# zzh.net
KiCad netlist of a schematic drawn in EAGLE
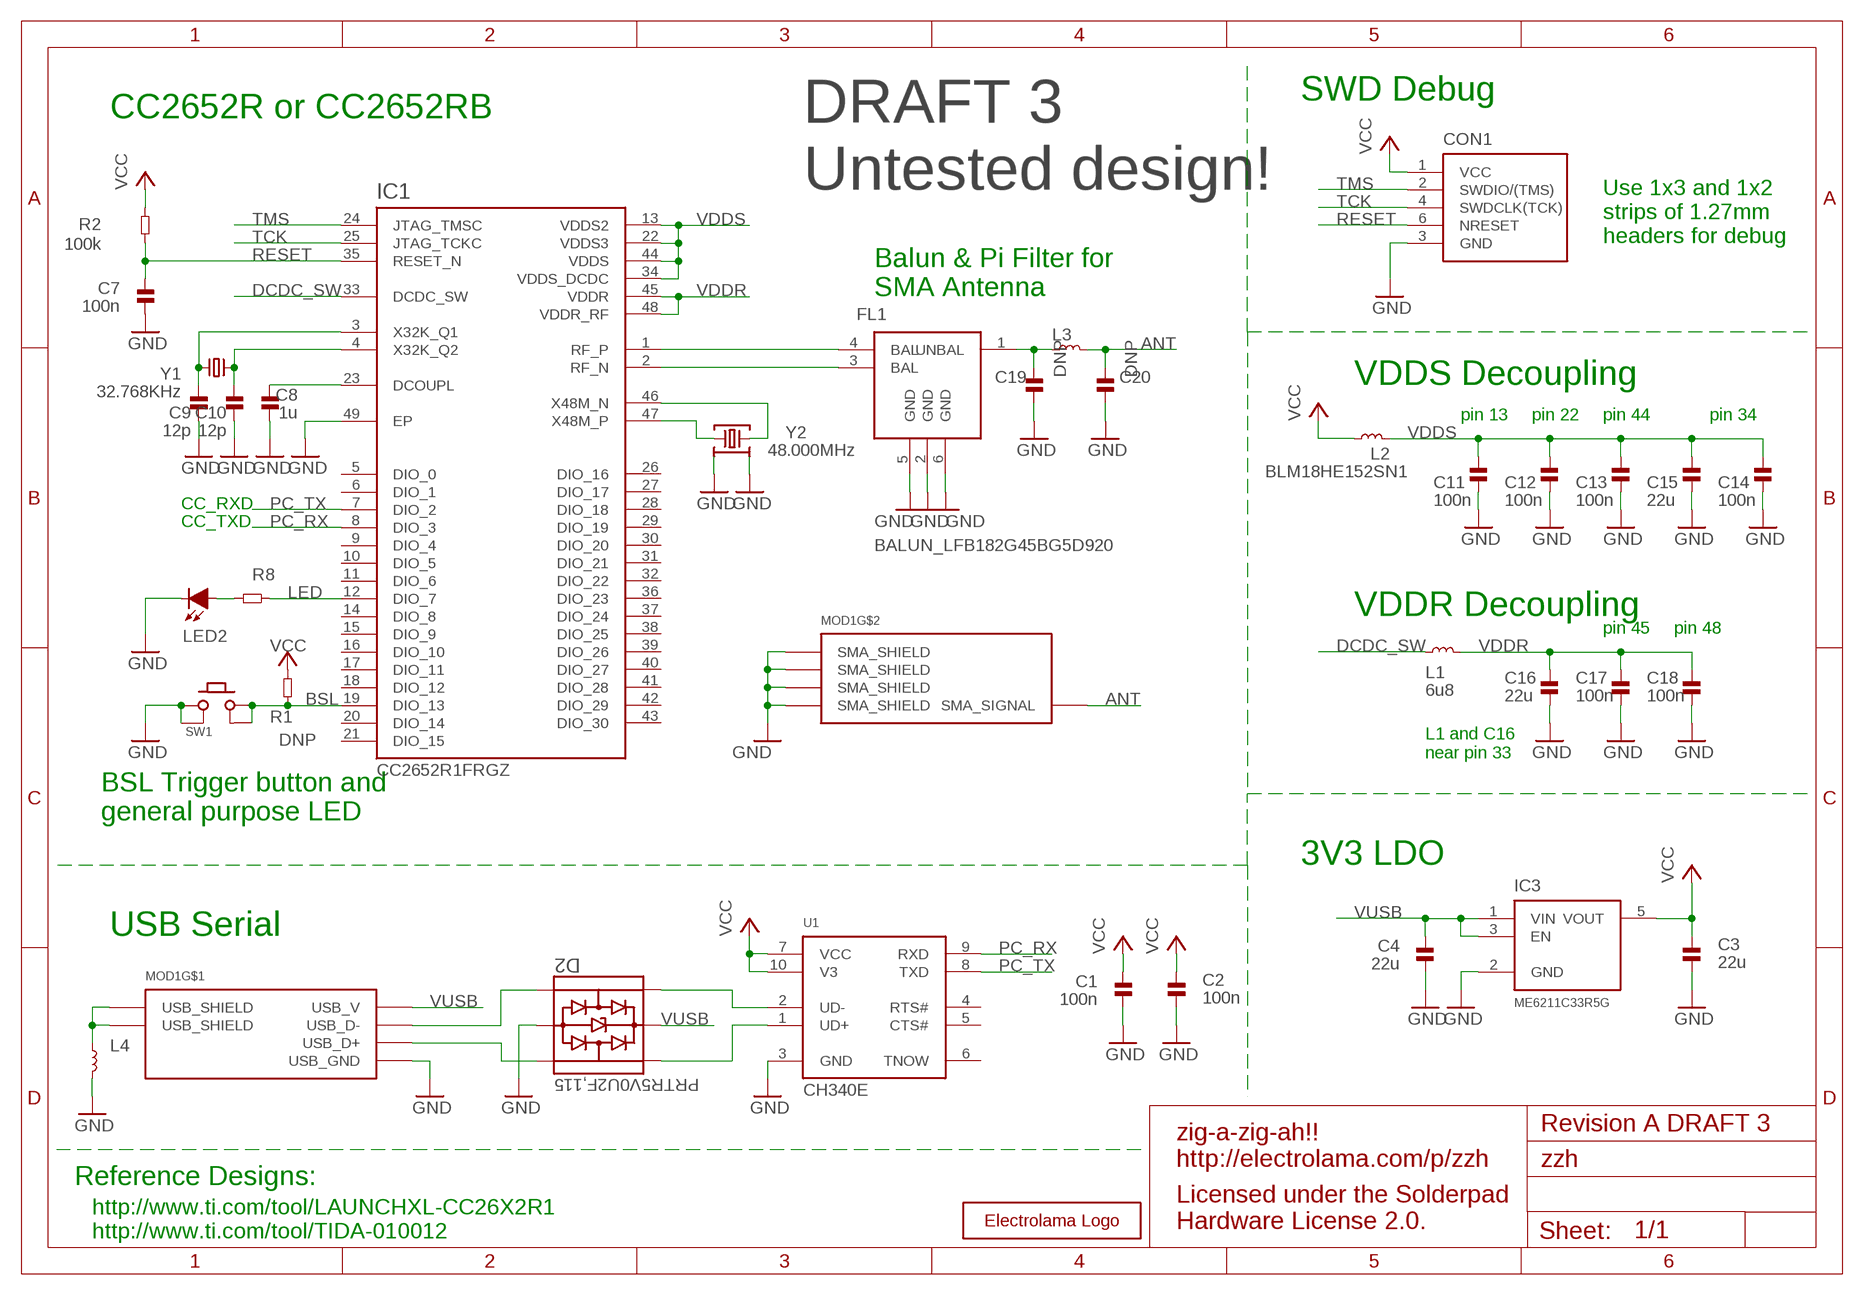
[diagram p0: schematic, sheet 1]

(export (version "E")
  (design (tool "Eeschema 10.0.6"))
  (components
    (comp (ref "C1")
      (value "100n")
      (footprint "eagle-import:_PKG_C_0402")
      (libsource (lib "eagle-import") (part "CAP-0402"))
    )
    (comp (ref "C2")
      (value "100n")
      (footprint "eagle-import:_PKG_C_0402")
      (libsource (lib "eagle-import") (part "CAP-0402"))
    )
    (comp (ref "C3")
      (value "22u")
      (footprint "eagle-import:_PKG_C_0805")
      (libsource (lib "eagle-import") (part "CAP-0805"))
    )
    (comp (ref "C4")
      (value "22u")
      (footprint "eagle-import:_PKG_C_0805")
      (libsource (lib "eagle-import") (part "CAP-0805"))
    )
    (comp (ref "C7")
      (value "100n")
      (footprint "eagle-import:_PKG_C_0402")
      (libsource (lib "eagle-import") (part "CAP-0402"))
    )
    (comp (ref "C8")
      (value "1u")
      (footprint "eagle-import:_PKG_C_0402")
      (libsource (lib "eagle-import") (part "CAP-0402"))
    )
    (comp (ref "C9")
      (value "12p")
      (footprint "eagle-import:_PKG_C_0402")
      (libsource (lib "eagle-import") (part "CAP-0402"))
    )
    (comp (ref "C10")
      (value "12p")
      (footprint "eagle-import:_PKG_C_0402")
      (libsource (lib "eagle-import") (part "CAP-0402"))
    )
    (comp (ref "C11")
      (value "100n")
      (footprint "eagle-import:_PKG_C_0402")
      (libsource (lib "eagle-import") (part "CAP-0402"))
    )
    (comp (ref "C12")
      (value "100n")
      (footprint "eagle-import:_PKG_C_0402")
      (libsource (lib "eagle-import") (part "CAP-0402"))
    )
    (comp (ref "C13")
      (value "100n")
      (footprint "eagle-import:_PKG_C_0402")
      (libsource (lib "eagle-import") (part "CAP-0402"))
    )
    (comp (ref "C14")
      (value "100n")
      (footprint "eagle-import:_PKG_C_0402")
      (libsource (lib "eagle-import") (part "CAP-0402"))
    )
    (comp (ref "C15")
      (value "22u")
      (footprint "eagle-import:_PKG_C_0805")
      (libsource (lib "eagle-import") (part "CAP-0805"))
    )
    (comp (ref "C16")
      (value "22u")
      (footprint "eagle-import:_PKG_C_0805")
      (libsource (lib "eagle-import") (part "CAP-0805"))
    )
    (comp (ref "C17")
      (value "100n")
      (footprint "eagle-import:_PKG_C_0402")
      (libsource (lib "eagle-import") (part "CAP-0402"))
    )
    (comp (ref "C18")
      (value "100n")
      (footprint "eagle-import:_PKG_C_0402")
      (libsource (lib "eagle-import") (part "CAP-0402"))
    )
    (comp (ref "C19")
      (value "DNP")
      (footprint "eagle-import:_PKG_C_0402")
      (libsource (lib "eagle-import") (part "CAP-0402"))
    )
    (comp (ref "C20")
      (value "DNP")
      (footprint "eagle-import:_PKG_C_0402")
      (libsource (lib "eagle-import") (part "CAP-0402"))
    )
    (comp (ref "CON1")
      (value "DEBUG_CORTEX-SWD-5PIN-CUT5")
      (footprint "eagle-import:DEBUG_CORTEX_5PIN")
      (libsource (lib "eagle-import") (part "DEBUG_CORTEX-SWD-5PIN-CUT5"))
    )
    (comp (ref "D2")
      (value "PRTR5V0U2F,115")
      (footprint "eagle-import:_PKG_SOT886_JEDEC-MO-252")
      (fields
        (field (name "MOUSER_PART_NUMBER") "771-PRTR5V0U2F-T/R")
        (field (name "RS_PART_NUMBER") "8166931P")
      )
      (libsource (lib "eagle-import") (part "DIODE-TVS-PRTR5V0U2F{dblquote}"))
    )
    (comp (ref "FL1")
      (value "BALUN_LFB182G45BG5D920")
      (footprint "eagle-import:LFB182G45BG5D920")
      (fields
        (field (name "MANUFACTURER_PART_NUMBER") "LFB182G45BG5D920")
        (field (name "MOUSER_PART_NUMBER") "81-LFB182G45BG5D920")
      )
      (libsource (lib "eagle-import") (part "BALUN_LFB182G45BG5D920"))
    )
    (comp (ref "IC1")
      (value "CC2652R1FRGZ")
      (footprint "eagle-import:QFN50P700X700X100-49N")
      (fields
        (field (name "MANUFACTURER_PART_NUMBER") "CC2652R1FRGZT")
        (field (name "MOUSER_PART_NUMBER") "595-CC2652R1FRGZT")
      )
      (libsource (lib "eagle-import") (part "WMCU-CC2652R1FRGZ"))
    )
    (comp (ref "IC3")
      (value "ME6211C33R5G")
      (footprint "eagle-import:SOT65P212X110-5N")
      (libsource (lib "eagle-import") (part "POWER-LDO-ME6211C33R5G"))
    )
    (comp (ref "L1")
      (value "6u8")
      (footprint "eagle-import:_PKG_C_0805")
      (libsource (lib "eagle-import") (part "INDUCTOR-0805"))
    )
    (comp (ref "L2")
      (value "BLM18HE152SN1")
      (footprint "eagle-import:_PKG_L_0603")
      (libsource (lib "eagle-import") (part "INDUCTOR-0603"))
    )
    (comp (ref "L3")
      (value "INDUCTOR-0402")
      (footprint "eagle-import:_PKG_L_0402")
      (libsource (lib "eagle-import") (part "INDUCTOR-0402"))
    )
    (comp (ref "L4")
      (value "INDUCTOR-0402")
      (footprint "eagle-import:_PKG_L_0402")
      (libsource (lib "eagle-import") (part "INDUCTOR-0402"))
    )
    (comp (ref "LED2")
      (value "LED-0603")
      (footprint "eagle-import:_PKG_LED_0603")
      (libsource (lib "eagle-import") (part "LED-0603"))
    )
    (comp (ref "MOD1")
      (value "ZZH_MODULE")
      (footprint "eagle-import:ZZH_MODULE")
      (libsource (lib "eagle-import") (part "ZZH_MODULE"))
    )
    (comp (ref "R1")
      (value "DNP")
      (footprint "eagle-import:_PKG_C_0402")
      (libsource (lib "eagle-import") (part "RES-0402"))
    )
    (comp (ref "R2")
      (value "100k")
      (footprint "eagle-import:_PKG_C_0402")
      (libsource (lib "eagle-import") (part "RES-0402"))
    )
    (comp (ref "R8")
      (value "RES-0402")
      (footprint "eagle-import:_PKG_C_0402")
      (libsource (lib "eagle-import") (part "RES-0402"))
    )
    (comp (ref "SW1")
      (value "K2-1177SW-D4DW-06")
      (footprint "eagle-import:K2-1177SW-D4DW-06")
      (libsource (lib "eagle-import") (part "PUSHBUTTON-K2-1177SW-D4DW-06"))
    )
    (comp (ref "U$5")
      (value "LOGO-ELECTROLAMA")
      (footprint "eagle-import:ELECTROLAMA")
      (libsource (lib "eagle-import") (part "LOGO-ELECTROLAMA"))
    )
    (comp (ref "U1")
      (value "CH340E")
      (footprint "eagle-import:_PKG_MSOP10_TI-DGS10")
      (libsource (lib "eagle-import") (part "INTERFACE-CH340E"))
    )
    (comp (ref "Y1")
      (value "32.768KHz")
      (footprint "eagle-import:XTAL-2P-3215")
      (fields (field (name "LCSC_PART") "C32346") (field (name "MFG_PART") "Q13FC1350000400"))
      (libsource (lib "eagle-import") (part "32.768KHZ_Q13FC1350000400"))
    )
    (comp (ref "Y2")
      (value "48.000MHz")
      (footprint "eagle-import:XTAL-4P-2016")
      (fields (field (name "DIGIKEY_PART") "1253-2042-1-ND") (field (name "MFG_PART") "CX2016DB48000C0FPLC1"))
      (libsource (lib "eagle-import") (part "48.000MHZ_CX2016DB48000C0FPLC1"))
    )
  )
  (nets
    (net (code "1") (name "/ANT") (class "Default")
      (node (ref "C20") (pin "2") (pinfunction "2_2") (pintype "passive"))
      (node (ref "L3") (pin "2") (pinfunction "2_2") (pintype "passive"))
      (node (ref "MOD1") (pin "SMA_SIGNAL") (pinfunction "SMA_SIGNAL_SMA_SIGNAL") (pintype "bidirectional"))
    )
    (net (code "2") (name "/BSL") (class "Default")
      (node (ref "IC1") (pin "19") (pinfunction "DIO_13_19") (pintype "bidirectional"))
      (node (ref "R1") (pin "2") (pinfunction "2_2") (pintype "passive"))
      (node (ref "SW1") (pin "3") (pinfunction "2_1_3") (pintype "bidirectional"))
      (node (ref "SW1") (pin "4") (pinfunction "2_2_4") (pintype "bidirectional"))
    )
    (net (code "3") (name "/DCDC_SW") (class "Default")
      (node (ref "IC1") (pin "33") (pinfunction "DCDC_SW_33") (pintype "bidirectional"))
      (node (ref "L1") (pin "1") (pinfunction "1_1") (pintype "passive"))
    )
    (net (code "4") (name "/LED") (class "Default")
      (node (ref "IC1") (pin "12") (pinfunction "DIO_7_12") (pintype "bidirectional"))
      (node (ref "R8") (pin "1") (pinfunction "1_1") (pintype "passive"))
    )
    (net (code "6") (name "/PC_RX") (class "Default")
      (node (ref "IC1") (pin "8") (pinfunction "DIO_3_8") (pintype "bidirectional"))
      (node (ref "U1") (pin "9") (pinfunction "RXD_9") (pintype "bidirectional"))
    )
    (net (code "7") (name "/PC_TX") (class "Default")
      (node (ref "IC1") (pin "7") (pinfunction "DIO_2_7") (pintype "bidirectional"))
      (node (ref "U1") (pin "8") (pinfunction "TXD_8") (pintype "bidirectional"))
    )
    (net (code "8") (name "/RESET") (class "Default")
      (node (ref "C7") (pin "2") (pinfunction "2_2") (pintype "passive"))
      (node (ref "CON1") (pin "6") (pinfunction "NRESET_6") (pintype "bidirectional"))
      (node (ref "IC1") (pin "35") (pinfunction "RESET_N_35") (pintype "bidirectional"))
      (node (ref "R2") (pin "1") (pinfunction "1_1") (pintype "passive"))
    )
    (net (code "9") (name "/TCK") (class "Default")
      (node (ref "CON1") (pin "4") (pinfunction "SWDCLK(TCK)_4") (pintype "bidirectional"))
      (node (ref "IC1") (pin "25") (pinfunction "JTAG_TCKC_25") (pintype "bidirectional"))
    )
    (net (code "10") (name "/TMS") (class "Default")
      (node (ref "CON1") (pin "2") (pinfunction "SWDIO/(TMS)_2") (pintype "bidirectional"))
      (node (ref "IC1") (pin "24") (pinfunction "JTAG_TMSC_24") (pintype "bidirectional"))
    )
    (net (code "11") (name "/VDDR") (class "Default")
      (node (ref "C16") (pin "1") (pinfunction "1_1") (pintype "passive"))
      (node (ref "C17") (pin "1") (pinfunction "1_1") (pintype "passive"))
      (node (ref "C18") (pin "1") (pinfunction "1_1") (pintype "passive"))
      (node (ref "IC1") (pin "45") (pinfunction "VDDR_45") (pintype "bidirectional"))
      (node (ref "IC1") (pin "48") (pinfunction "VDDR_RF_48") (pintype "bidirectional"))
      (node (ref "L1") (pin "2") (pinfunction "2_2") (pintype "passive"))
    )
    (net (code "12") (name "/VDDS") (class "Default")
      (node (ref "C11") (pin "1") (pinfunction "1_1") (pintype "passive"))
      (node (ref "C12") (pin "1") (pinfunction "1_1") (pintype "passive"))
      (node (ref "C13") (pin "1") (pinfunction "1_1") (pintype "passive"))
      (node (ref "C14") (pin "1") (pinfunction "1_1") (pintype "passive"))
      (node (ref "C15") (pin "1") (pinfunction "1_1") (pintype "passive"))
      (node (ref "IC1") (pin "13") (pinfunction "VDDS2_13") (pintype "bidirectional"))
      (node (ref "IC1") (pin "22") (pinfunction "VDDS3_22") (pintype "bidirectional"))
      (node (ref "IC1") (pin "34") (pinfunction "VDDS_DCDC_34") (pintype "bidirectional"))
      (node (ref "IC1") (pin "44") (pinfunction "VDDS_44") (pintype "bidirectional"))
      (node (ref "L2") (pin "2") (pinfunction "2_2") (pintype "passive"))
    )
    (net (code "13") (name "/VUSB") (class "Default")
      (node (ref "C4") (pin "1") (pinfunction "1_1") (pintype "passive"))
      (node (ref "D2") (pin "5") (pinfunction "5_5") (pintype "passive"))
      (node (ref "IC3") (pin "1") (pinfunction "VIN_1") (pintype "bidirectional"))
      (node (ref "IC3") (pin "3") (pinfunction "EN_3") (pintype "bidirectional"))
      (node (ref "MOD1") (pin "USB_V") (pinfunction "USB_V_USB_V") (pintype "bidirectional"))
    )
    (net (code "14") (name "GND") (class "Default")
      (node (ref "C1") (pin "1") (pinfunction "1_1") (pintype "passive"))
      (node (ref "C10") (pin "1") (pinfunction "1_1") (pintype "passive"))
      (node (ref "C11") (pin "2") (pinfunction "2_2") (pintype "passive"))
      (node (ref "C12") (pin "2") (pinfunction "2_2") (pintype "passive"))
      (node (ref "C13") (pin "2") (pinfunction "2_2") (pintype "passive"))
      (node (ref "C14") (pin "2") (pinfunction "2_2") (pintype "passive"))
      (node (ref "C15") (pin "2") (pinfunction "2_2") (pintype "passive"))
      (node (ref "C16") (pin "2") (pinfunction "2_2") (pintype "passive"))
      (node (ref "C17") (pin "2") (pinfunction "2_2") (pintype "passive"))
      (node (ref "C18") (pin "2") (pinfunction "2_2") (pintype "passive"))
      (node (ref "C19") (pin "1") (pinfunction "1_1") (pintype "passive"))
      (node (ref "C2") (pin "1") (pinfunction "1_1") (pintype "passive"))
      (node (ref "C20") (pin "1") (pinfunction "1_1") (pintype "passive"))
      (node (ref "C3") (pin "2") (pinfunction "2_2") (pintype "passive"))
      (node (ref "C4") (pin "2") (pinfunction "2_2") (pintype "passive"))
      (node (ref "C7") (pin "1") (pinfunction "1_1") (pintype "passive"))
      (node (ref "C8") (pin "1") (pinfunction "1_1") (pintype "passive"))
      (node (ref "C9") (pin "1") (pinfunction "1_1") (pintype "passive"))
      (node (ref "CON1") (pin "3") (pinfunction "GND_3") (pintype "bidirectional"))
      (node (ref "D2") (pin "2") (pinfunction "2_2") (pintype "passive"))
      (node (ref "FL1") (pin "2") (pinfunction "GND_2") (pintype "bidirectional"))
      (node (ref "FL1") (pin "5") (pinfunction "GND_5") (pintype "bidirectional"))
      (node (ref "FL1") (pin "6") (pinfunction "GND_6") (pintype "bidirectional"))
      (node (ref "IC1") (pin "49") (pinfunction "EP_49") (pintype "bidirectional"))
      (node (ref "IC3") (pin "2") (pinfunction "GND_2") (pintype "bidirectional"))
      (node (ref "L4") (pin "2") (pinfunction "2_2") (pintype "passive"))
      (node (ref "LED2") (pin "C") (pinfunction "C_C") (pintype "passive"))
      (node (ref "MOD1") (pin "SMA_SHIELD_1") (pinfunction "SMA_SHIELD_SMA_SHIELD_1") (pintype "bidirectional"))
      (node (ref "MOD1") (pin "SMA_SHIELD_2") (pinfunction "SMA_SHIELD_SMA_SHIELD_2") (pintype "bidirectional"))
      (node (ref "MOD1") (pin "SMA_SHIELD_3") (pinfunction "SMA_SHIELD_SMA_SHIELD_3") (pintype "bidirectional"))
      (node (ref "MOD1") (pin "SMA_SHIELD_4") (pinfunction "SMA_SHIELD_SMA_SHIELD_4") (pintype "bidirectional"))
      (node (ref "MOD1") (pin "USB_GND") (pinfunction "USB_GND_USB_GND") (pintype "bidirectional"))
      (node (ref "SW1") (pin "1") (pinfunction "1_1_1") (pintype "bidirectional"))
      (node (ref "SW1") (pin "2") (pinfunction "1_2_2") (pintype "bidirectional"))
      (node (ref "U1") (pin "3") (pinfunction "GND_3") (pintype "bidirectional"))
      (node (ref "Y2") (pin "2") (pinfunction "2_2") (pintype "bidirectional"))
      (node (ref "Y2") (pin "4") (pinfunction "4_4") (pintype "bidirectional"))
    )
    (net (code "15") (name "Net-(D2-Pad1)") (class "Default")
      (node (ref "D2") (pin "1") (pinfunction "1_1") (pintype "passive"))
      (node (ref "MOD1") (pin "USB_D+") (pinfunction "USB_D+_USB_D+") (pintype "bidirectional"))
    )
    (net (code "16") (name "Net-(D2-Pad3)") (class "Default")
      (node (ref "D2") (pin "3") (pinfunction "3_3") (pintype "passive"))
      (node (ref "MOD1") (pin "USB_D-") (pinfunction "USB_D-_USB_D-") (pintype "bidirectional"))
    )
    (net (code "17") (name "Net-(FL1-UNBAL)") (class "Default")
      (node (ref "C19") (pin "2") (pinfunction "2_2") (pintype "passive"))
      (node (ref "FL1") (pin "1") (pinfunction "UNBAL_1") (pintype "bidirectional"))
      (node (ref "L3") (pin "1") (pinfunction "1_1") (pintype "passive"))
    )
    (net (code "18") (name "Net-(IC1-DCOUPL)") (class "Default")
      (node (ref "C8") (pin "2") (pinfunction "2_2") (pintype "passive"))
      (node (ref "IC1") (pin "23") (pinfunction "DCOUPL_23") (pintype "bidirectional"))
    )
    (net (code "19") (name "Net-(IC1-RF_N)") (class "Default")
      (node (ref "FL1") (pin "3") (pinfunction "BAL_3") (pintype "bidirectional"))
      (node (ref "IC1") (pin "2") (pinfunction "RF_N_2") (pintype "bidirectional"))
    )
    (net (code "20") (name "Net-(IC1-RF_P)") (class "Default")
      (node (ref "FL1") (pin "4") (pinfunction "BAL_4") (pintype "bidirectional"))
      (node (ref "IC1") (pin "1") (pinfunction "RF_P_1") (pintype "bidirectional"))
    )
    (net (code "21") (name "Net-(IC1-X32K_Q1)") (class "Default")
      (node (ref "C9") (pin "2") (pinfunction "2_2") (pintype "passive"))
      (node (ref "IC1") (pin "3") (pinfunction "X32K_Q1_3") (pintype "bidirectional"))
      (node (ref "Y1") (pin "1") (pinfunction "1_1") (pintype "passive"))
    )
    (net (code "22") (name "Net-(IC1-X32K_Q2)") (class "Default")
      (node (ref "C10") (pin "2") (pinfunction "2_2") (pintype "passive"))
      (node (ref "IC1") (pin "4") (pinfunction "X32K_Q2_4") (pintype "bidirectional"))
      (node (ref "Y1") (pin "2") (pinfunction "2_2") (pintype "passive"))
    )
    (net (code "23") (name "Net-(IC1-X48M_N)") (class "Default")
      (node (ref "IC1") (pin "46") (pinfunction "X48M_N_46") (pintype "bidirectional"))
      (node (ref "Y2") (pin "3") (pinfunction "3_3") (pintype "passive"))
    )
    (net (code "24") (name "Net-(IC1-X48M_P)") (class "Default")
      (node (ref "IC1") (pin "47") (pinfunction "X48M_P_47") (pintype "bidirectional"))
      (node (ref "Y2") (pin "1") (pinfunction "1_1") (pintype "passive"))
    )
    (net (code "25") (name "Net-(L4-Pad1)") (class "Default")
      (node (ref "L4") (pin "1") (pinfunction "1_1") (pintype "passive"))
      (node (ref "MOD1") (pin "USB_SHIELD_1") (pinfunction "USB_SHIELD_USB_SHIELD_1") (pintype "bidirectional"))
      (node (ref "MOD1") (pin "USB_SHIELD_2") (pinfunction "USB_SHIELD_USB_SHIELD_2") (pintype "bidirectional"))
    )
    (net (code "26") (name "Net-(LED2-PadA)") (class "Default")
      (node (ref "LED2") (pin "A") (pinfunction "A_A") (pintype "passive"))
      (node (ref "R8") (pin "2") (pinfunction "2_2") (pintype "passive"))
    )
    (net (code "27") (name "Net-(U1-UD+)") (class "Default")
      (node (ref "D2") (pin "6") (pinfunction "6_6") (pintype "passive"))
      (node (ref "U1") (pin "1") (pinfunction "UD+_1") (pintype "bidirectional"))
    )
    (net (code "28") (name "Net-(U1-UD-)") (class "Default")
      (node (ref "D2") (pin "4") (pinfunction "4_4") (pintype "passive"))
      (node (ref "U1") (pin "2") (pinfunction "UD-_2") (pintype "bidirectional"))
    )
    (net (code "29") (name "VCC") (class "Default")
      (node (ref "C1") (pin "2") (pinfunction "2_2") (pintype "passive"))
      (node (ref "C2") (pin "2") (pinfunction "2_2") (pintype "passive"))
      (node (ref "C3") (pin "1") (pinfunction "1_1") (pintype "passive"))
      (node (ref "CON1") (pin "1") (pinfunction "VCC_1") (pintype "bidirectional"))
      (node (ref "IC3") (pin "5") (pinfunction "VOUT_5") (pintype "bidirectional"))
      (node (ref "L2") (pin "1") (pinfunction "1_1") (pintype "passive"))
      (node (ref "R1") (pin "1") (pinfunction "1_1") (pintype "passive"))
      (node (ref "R2") (pin "2") (pinfunction "2_2") (pintype "passive"))
      (node (ref "U1") (pin "10") (pinfunction "V3_10") (pintype "bidirectional"))
      (node (ref "U1") (pin "7") (pinfunction "VCC_7") (pintype "bidirectional"))
    )
    (net (code "30") (name "unconnected-(IC1-DIO_0-Pad5)") (class "Default")
      (node (ref "IC1") (pin "5") (pinfunction "DIO_0_5") (pintype "bidirectional"))
    )
    (net (code "31") (name "unconnected-(IC1-DIO_1-Pad6)") (class "Default")
      (node (ref "IC1") (pin "6") (pinfunction "DIO_1_6") (pintype "bidirectional"))
    )
    (net (code "32") (name "unconnected-(IC1-DIO_4-Pad9)") (class "Default")
      (node (ref "IC1") (pin "9") (pinfunction "DIO_4_9") (pintype "bidirectional"))
    )
    (net (code "33") (name "unconnected-(IC1-DIO_5-Pad10)") (class "Default")
      (node (ref "IC1") (pin "10") (pinfunction "DIO_5_10") (pintype "bidirectional"))
    )
    (net (code "34") (name "unconnected-(IC1-DIO_6-Pad11)") (class "Default")
      (node (ref "IC1") (pin "11") (pinfunction "DIO_6_11") (pintype "bidirectional"))
    )
    (net (code "35") (name "unconnected-(IC1-DIO_8-Pad14)") (class "Default")
      (node (ref "IC1") (pin "14") (pinfunction "DIO_8_14") (pintype "bidirectional"))
    )
    (net (code "36") (name "unconnected-(IC1-DIO_9-Pad15)") (class "Default")
      (node (ref "IC1") (pin "15") (pinfunction "DIO_9_15") (pintype "bidirectional"))
    )
    (net (code "37") (name "unconnected-(IC1-DIO_10-Pad16)") (class "Default")
      (node (ref "IC1") (pin "16") (pinfunction "DIO_10_16") (pintype "bidirectional"))
    )
    (net (code "38") (name "unconnected-(IC1-DIO_11-Pad17)") (class "Default")
      (node (ref "IC1") (pin "17") (pinfunction "DIO_11_17") (pintype "bidirectional"))
    )
    (net (code "39") (name "unconnected-(IC1-DIO_12-Pad18)") (class "Default")
      (node (ref "IC1") (pin "18") (pinfunction "DIO_12_18") (pintype "bidirectional"))
    )
    (net (code "40") (name "unconnected-(IC1-DIO_14-Pad20)") (class "Default")
      (node (ref "IC1") (pin "20") (pinfunction "DIO_14_20") (pintype "bidirectional"))
    )
    (net (code "41") (name "unconnected-(IC1-DIO_15-Pad21)") (class "Default")
      (node (ref "IC1") (pin "21") (pinfunction "DIO_15_21") (pintype "bidirectional"))
    )
    (net (code "42") (name "unconnected-(IC1-DIO_16-Pad26)") (class "Default")
      (node (ref "IC1") (pin "26") (pinfunction "DIO_16_26") (pintype "bidirectional"))
    )
    (net (code "43") (name "unconnected-(IC1-DIO_17-Pad27)") (class "Default")
      (node (ref "IC1") (pin "27") (pinfunction "DIO_17_27") (pintype "bidirectional"))
    )
    (net (code "44") (name "unconnected-(IC1-DIO_18-Pad28)") (class "Default")
      (node (ref "IC1") (pin "28") (pinfunction "DIO_18_28") (pintype "bidirectional"))
    )
    (net (code "45") (name "unconnected-(IC1-DIO_19-Pad29)") (class "Default")
      (node (ref "IC1") (pin "29") (pinfunction "DIO_19_29") (pintype "bidirectional"))
    )
    (net (code "46") (name "unconnected-(IC1-DIO_20-Pad30)") (class "Default")
      (node (ref "IC1") (pin "30") (pinfunction "DIO_20_30") (pintype "bidirectional"))
    )
    (net (code "47") (name "unconnected-(IC1-DIO_21-Pad31)") (class "Default")
      (node (ref "IC1") (pin "31") (pinfunction "DIO_21_31") (pintype "bidirectional"))
    )
    (net (code "48") (name "unconnected-(IC1-DIO_22-Pad32)") (class "Default")
      (node (ref "IC1") (pin "32") (pinfunction "DIO_22_32") (pintype "bidirectional"))
    )
    (net (code "49") (name "unconnected-(IC1-DIO_23-Pad36)") (class "Default")
      (node (ref "IC1") (pin "36") (pinfunction "DIO_23_36") (pintype "bidirectional"))
    )
    (net (code "50") (name "unconnected-(IC1-DIO_24-Pad37)") (class "Default")
      (node (ref "IC1") (pin "37") (pinfunction "DIO_24_37") (pintype "bidirectional"))
    )
    (net (code "51") (name "unconnected-(IC1-DIO_25-Pad38)") (class "Default")
      (node (ref "IC1") (pin "38") (pinfunction "DIO_25_38") (pintype "bidirectional"))
    )
    (net (code "52") (name "unconnected-(IC1-DIO_26-Pad39)") (class "Default")
      (node (ref "IC1") (pin "39") (pinfunction "DIO_26_39") (pintype "bidirectional"))
    )
    (net (code "53") (name "unconnected-(IC1-DIO_27-Pad40)") (class "Default")
      (node (ref "IC1") (pin "40") (pinfunction "DIO_27_40") (pintype "bidirectional"))
    )
    (net (code "54") (name "unconnected-(IC1-DIO_28-Pad41)") (class "Default")
      (node (ref "IC1") (pin "41") (pinfunction "DIO_28_41") (pintype "bidirectional"))
    )
    (net (code "55") (name "unconnected-(IC1-DIO_29-Pad42)") (class "Default")
      (node (ref "IC1") (pin "42") (pinfunction "DIO_29_42") (pintype "bidirectional"))
    )
    (net (code "56") (name "unconnected-(IC1-DIO_30-Pad43)") (class "Default")
      (node (ref "IC1") (pin "43") (pinfunction "DIO_30_43") (pintype "bidirectional"))
    )
    (net (code "57") (name "unconnected-(U1-CTS#-Pad5)") (class "Default")
      (node (ref "U1") (pin "5") (pinfunction "CTS#_5") (pintype "bidirectional"))
    )
    (net (code "58") (name "unconnected-(U1-RTS#-Pad4)") (class "Default")
      (node (ref "U1") (pin "4") (pinfunction "RTS#_4") (pintype "bidirectional"))
    )
    (net (code "59") (name "unconnected-(U1-TNOW-Pad6)") (class "Default")
      (node (ref "U1") (pin "6") (pinfunction "TNOW_6") (pintype "bidirectional"))
    )
  )
)
